# HP4-1.net
KiCad netlist of a schematic drawn in EAGLE
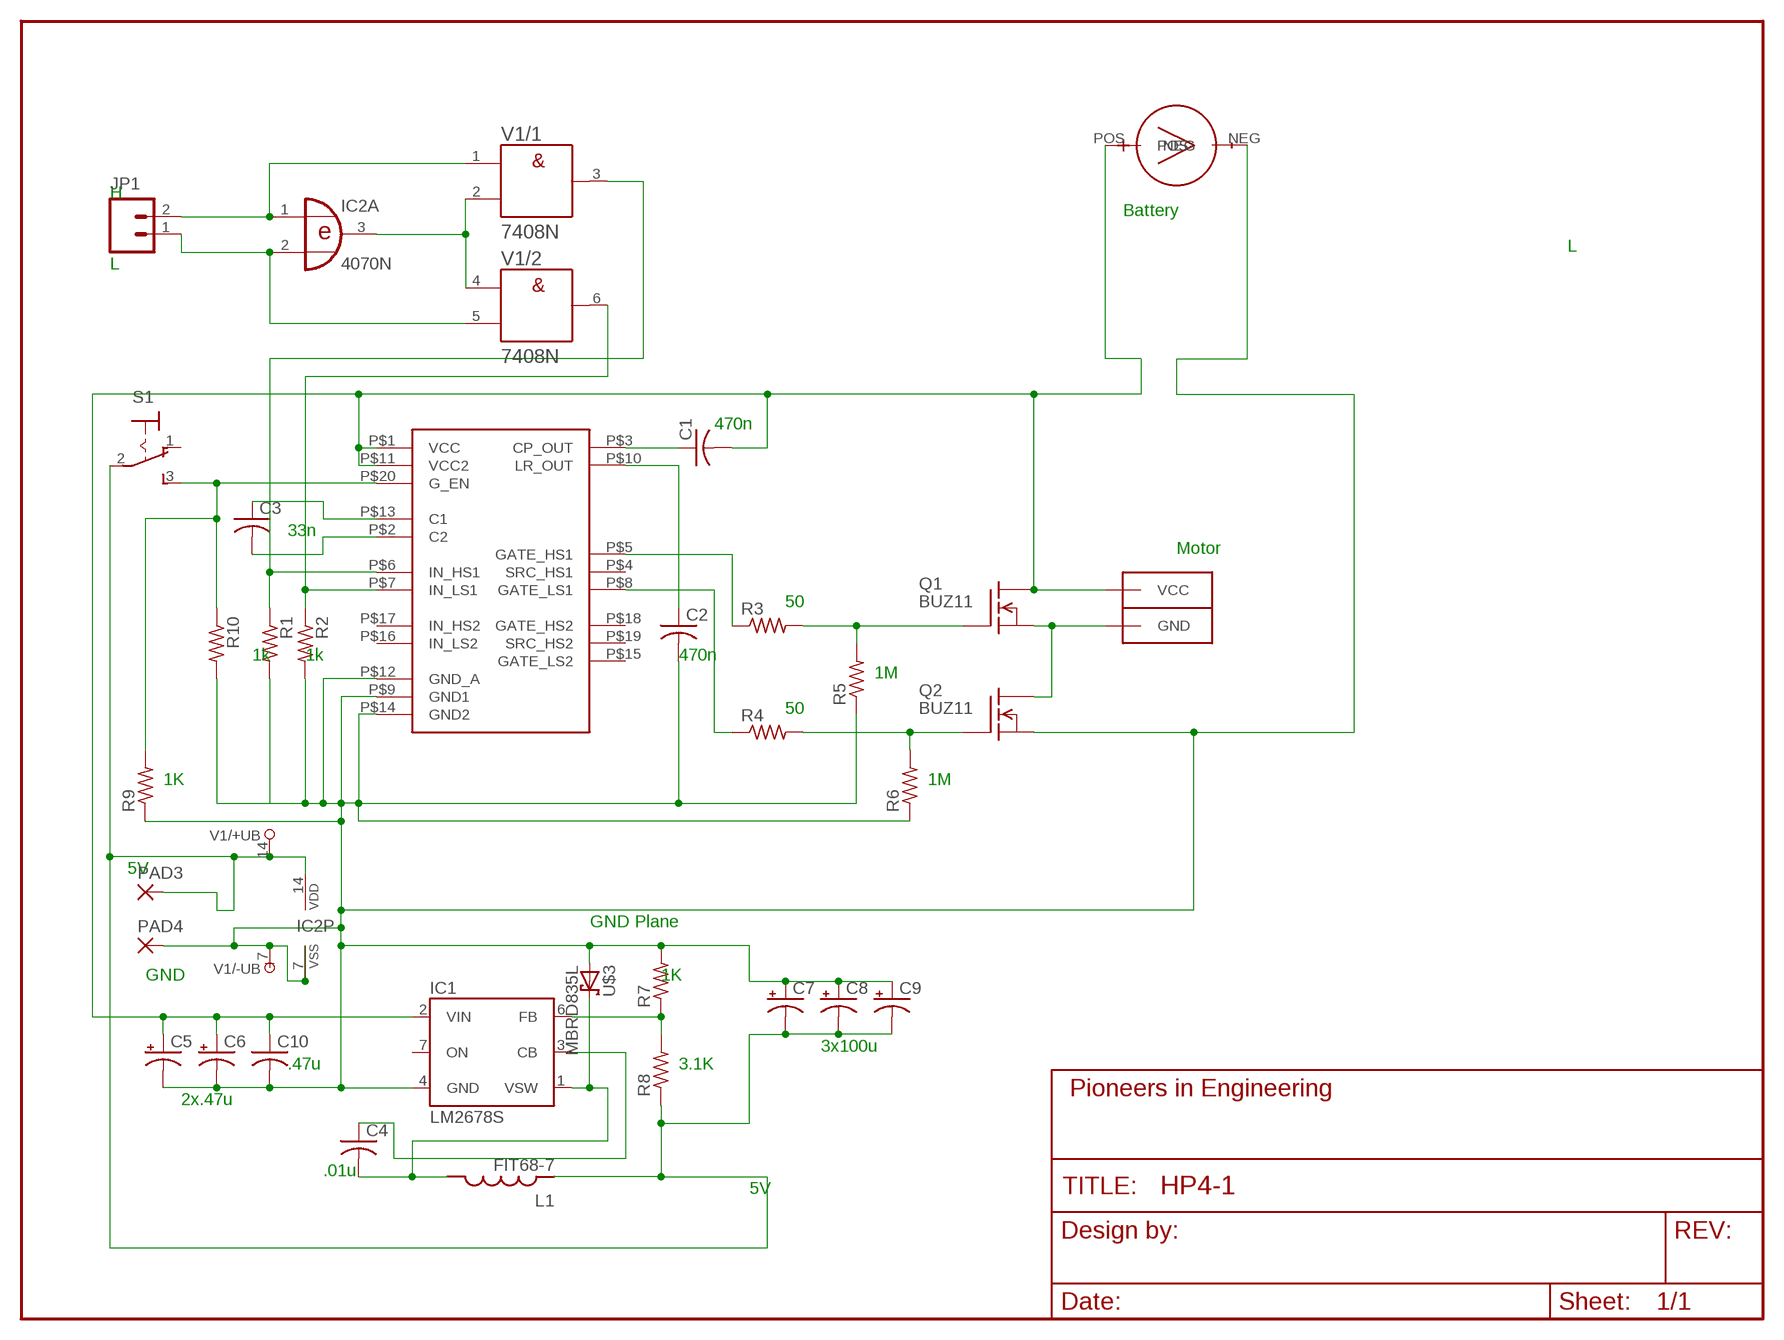
[diagram p0: schematic, sheet 1]

(export (version "E")
  (design (tool "Eeschema 10.0.6"))
  (components
    (comp (ref "C1")
      (value "C-USC1206")
      (footprint "eagle-import:C1206")
      (libsource (lib "eagle-import") (part "C-USC1206"))
    )
    (comp (ref "C2")
      (value "C-USC1206")
      (footprint "eagle-import:C1206")
      (libsource (lib "eagle-import") (part "C-USC1206"))
    )
    (comp (ref "C3")
      (value "C-USC1206")
      (footprint "eagle-import:C1206")
      (libsource (lib "eagle-import") (part "C-USC1206"))
    )
    (comp (ref "C4")
      (value "C-US025-024X044")
      (footprint "eagle-import:C025-024X044")
      (libsource (lib "eagle-import") (part "C-US025-024X044"))
    )
    (comp (ref "C5")
      (value "CPOL-USCT6032")
      (footprint "eagle-import:CT6032")
      (libsource (lib "eagle-import") (part "CPOL-USCT6032"))
    )
    (comp (ref "C6")
      (value "CPOL-USCT6032")
      (footprint "eagle-import:CT6032")
      (libsource (lib "eagle-import") (part "CPOL-USCT6032"))
    )
    (comp (ref "C7")
      (value "CPOL-USCT6032")
      (footprint "eagle-import:CT6032")
      (libsource (lib "eagle-import") (part "CPOL-USCT6032"))
    )
    (comp (ref "C8")
      (value "CPOL-USCT6032")
      (footprint "eagle-import:CT6032")
      (libsource (lib "eagle-import") (part "CPOL-USCT6032"))
    )
    (comp (ref "C9")
      (value "CPOL-USCT6032")
      (footprint "eagle-import:CT6032")
      (libsource (lib "eagle-import") (part "CPOL-USCT6032"))
    )
    (comp (ref "C10")
      (value "C-USC1206")
      (footprint "eagle-import:C1206")
      (libsource (lib "eagle-import") (part "C-USC1206"))
    )
    (comp (ref "IC1")
      (value "LM2678S")
      (footprint "eagle-import:TO263-7")
      (libsource (lib "eagle-import") (part "LM2678S"))
    )
    (comp (ref "IC2")
      (value "4070N")
      (footprint "eagle-import:DIL14")
      (libsource (lib "eagle-import") (part "4070N"))
    )
    (comp (ref "JP1")
      (value "M02PTH")
      (footprint "eagle-import:1X02")
      (libsource (lib "eagle-import") (part "M02PTH"))
    )
    (comp (ref "L1")
      (value "FIT68-7")
      (footprint "eagle-import:FIT68-7")
      (libsource (lib "eagle-import") (part "FIT68-7"))
    )
    (comp (ref "MOTOR")
      (value "ANDERSON_PP_DOUBLEHORIZONTAL")
      (footprint "eagle-import:ANDERSON_PP_DOUB_HORZ")
      (libsource (lib "eagle-import") (part "ANDERSON_PP_DOUBLEHORIZONTAL"))
    )
    (comp (ref "PAD3")
      (value "3,17/1,3")
      (footprint "eagle-import:3,17_1,3")
      (libsource (lib "eagle-import") (part "3,17/1,3"))
    )
    (comp (ref "PAD4")
      (value "3,17/1,3")
      (footprint "eagle-import:3,17_1,3")
      (libsource (lib "eagle-import") (part "3,17/1,3"))
    )
    (comp (ref "Q1")
      (value "BUZ11")
      (footprint "eagle-import:TO220")
      (libsource (lib "eagle-import") (part "BUZ11"))
    )
    (comp (ref "Q2")
      (value "BUZ11")
      (footprint "eagle-import:TO220")
      (libsource (lib "eagle-import") (part "BUZ11"))
    )
    (comp (ref "R1")
      (value "R-US_M1206")
      (footprint "eagle-import:M1206")
      (libsource (lib "eagle-import") (part "R-US_M1206"))
    )
    (comp (ref "R2")
      (value "R-US_M1206")
      (footprint "eagle-import:M1206")
      (libsource (lib "eagle-import") (part "R-US_M1206"))
    )
    (comp (ref "R3")
      (value "R-US_M1206")
      (footprint "eagle-import:M1206")
      (libsource (lib "eagle-import") (part "R-US_M1206"))
    )
    (comp (ref "R4")
      (value "R-US_M1206")
      (footprint "eagle-import:M1206")
      (libsource (lib "eagle-import") (part "R-US_M1206"))
    )
    (comp (ref "R5")
      (value "R-US_M1206")
      (footprint "eagle-import:M1206")
      (libsource (lib "eagle-import") (part "R-US_M1206"))
    )
    (comp (ref "R6")
      (value "R-US_M1206")
      (footprint "eagle-import:M1206")
      (libsource (lib "eagle-import") (part "R-US_M1206"))
    )
    (comp (ref "R7")
      (value "R-US_R1206")
      (footprint "eagle-import:R1206")
      (libsource (lib "eagle-import") (part "R-US_R1206"))
    )
    (comp (ref "R8")
      (value "R-US_R1206")
      (footprint "eagle-import:R1206")
      (libsource (lib "eagle-import") (part "R-US_R1206"))
    )
    (comp (ref "R9")
      (value "R-US_R1206")
      (footprint "eagle-import:R1206")
      (libsource (lib "eagle-import") (part "R-US_R1206"))
    )
    (comp (ref "R10")
      (value "R-US_M1206")
      (footprint "eagle-import:M1206")
      (libsource (lib "eagle-import") (part "R-US_M1206"))
    )
    (comp (ref "S1")
      (value "320-916")
      (footprint "eagle-import:320-916")
      (libsource (lib "eagle-import") (part "320-916"))
    )
    (comp (ref "U$1")
      (value "MC33883DIL20_600MIL_CARRIER")
      (footprint "eagle-import:DIL20_600MIL")
      (libsource (lib "eagle-import") (part "MC33883DIL20_600MIL_CARRIER"))
    )
    (comp (ref "U$3")
      (value "MBRD835L")
      (footprint "eagle-import:DPAK")
      (libsource (lib "eagle-import") (part "MBRD835L"))
    )
    (comp (ref "U$4")
      (value "BATT")
      (footprint "eagle-import:BATT")
      (libsource (lib "eagle-import") (part "BATT"))
    )
    (comp (ref "V1")
      (value "7408N")
      (footprint "eagle-import:DIL14")
      (libsource (lib "eagle-import") (part "7408N"))
    )
  )
  (nets
    (net (code "1") (name "Net-(IC1-CB)") (class "Default")
      (node (ref "C4") (pin "1") (pinfunction "1_1") (pintype "passive"))
      (node (ref "IC1") (pin "3") (pinfunction "CB_3") (pintype "input"))
    )
    (net (code "2") (name "Net-(IC1-FB)") (class "Default")
      (node (ref "IC1") (pin "6") (pinfunction "FB_6") (pintype "input"))
      (node (ref "R7") (pin "1") (pinfunction "1_1") (pintype "passive"))
      (node (ref "R8") (pin "2") (pinfunction "2_2") (pintype "passive"))
    )
    (net (code "3") (name "Net-(IC1-GND)") (class "Default")
      (node (ref "C10") (pin "2") (pinfunction "2_2") (pintype "passive"))
      (node (ref "C2") (pin "2") (pinfunction "2_2") (pintype "passive"))
      (node (ref "C5") (pin "-") (pinfunction "-_-") (pintype "passive"))
      (node (ref "C6") (pin "-") (pinfunction "-_-") (pintype "passive"))
      (node (ref "C7") (pin "+") (pinfunction "+_+") (pintype "passive"))
      (node (ref "C8") (pin "+") (pinfunction "+_+") (pintype "passive"))
      (node (ref "C9") (pin "+") (pinfunction "+_+") (pintype "passive"))
      (node (ref "IC1") (pin "4") (pinfunction "GND_4") (pintype "power_in"))
      (node (ref "IC2") (pin "7") (pinfunction "VSS_7") (pintype "power_in"))
      (node (ref "PAD4") (pin "1") (pinfunction "P_1") (pintype "passive"))
      (node (ref "Q2") (pin "3") (pinfunction "S_3") (pintype "passive"))
      (node (ref "R1") (pin "2") (pinfunction "2_2") (pintype "passive"))
      (node (ref "R10") (pin "2") (pinfunction "2_2") (pintype "passive"))
      (node (ref "R2") (pin "2") (pinfunction "2_2") (pintype "passive"))
      (node (ref "R5") (pin "1") (pinfunction "1_1") (pintype "passive"))
      (node (ref "R6") (pin "1") (pinfunction "1_1") (pintype "passive"))
      (node (ref "R7") (pin "2") (pinfunction "2_2") (pintype "passive"))
      (node (ref "R9") (pin "1") (pinfunction "1_1") (pintype "passive"))
      (node (ref "U$1") (pin "P$12") (pinfunction "GND_A_P$12") (pintype "bidirectional"))
      (node (ref "U$1") (pin "P$14") (pinfunction "GND2_P$14") (pintype "bidirectional"))
      (node (ref "U$1") (pin "P$9") (pinfunction "GND1_P$9") (pintype "bidirectional"))
      (node (ref "U$3") (pin "P$1") (pinfunction "A_P$1") (pintype "passive"))
      (node (ref "U$3") (pin "P$2") (pinfunction "A_P$2") (pintype "passive"))
      (node (ref "U$4") (pin "NEG") (pinfunction "NEG_NEG") (pintype "bidirectional"))
      (node (ref "V1") (pin "7") (pinfunction "-UB_7") (pintype "power_in"))
    )
    (net (code "4") (name "Net-(IC1-VIN)") (class "Default")
      (node (ref "C1") (pin "2") (pinfunction "2_2") (pintype "passive"))
      (node (ref "C10") (pin "1") (pinfunction "1_1") (pintype "passive"))
      (node (ref "C5") (pin "+") (pinfunction "+_+") (pintype "passive"))
      (node (ref "C6") (pin "+") (pinfunction "+_+") (pintype "passive"))
      (node (ref "IC1") (pin "2") (pinfunction "VIN_2") (pintype "power_in"))
      (node (ref "MOTOR") (pin "PIN2") (pinfunction "VCC_PIN2") (pintype "bidirectional"))
      (node (ref "MOTOR") (pin "PIN2-LEAD") (pinfunction "VCC_PIN2-LEAD") (pintype "bidirectional"))
      (node (ref "Q1") (pin "2") (pinfunction "D_2") (pintype "passive"))
      (node (ref "U$1") (pin "P$1") (pinfunction "VCC_P$1") (pintype "bidirectional"))
      (node (ref "U$1") (pin "P$11") (pinfunction "VCC2_P$11") (pintype "bidirectional"))
      (node (ref "U$4") (pin "POS") (pinfunction "POS_POS") (pintype "bidirectional"))
    )
    (net (code "5") (name "Net-(IC1-VSW)") (class "Default")
      (node (ref "C4") (pin "2") (pinfunction "2_2") (pintype "passive"))
      (node (ref "IC1") (pin "1") (pinfunction "VSW_1") (pintype "output"))
      (node (ref "L1") (pin "P$2") (pinfunction "P$2_P$2") (pintype "bidirectional"))
      (node (ref "U$3") (pin "P$3") (pinfunction "C_P$3") (pintype "passive"))
    )
    (net (code "6") (name "Net-(IC2A-I0)") (class "Default")
      (node (ref "IC2") (pin "1") (pinfunction "I0_1") (pintype "input"))
      (node (ref "JP1") (pin "2") (pinfunction "2_2") (pintype "passive"))
      (node (ref "V1") (pin "1") (pinfunction "A_1") (pintype "input"))
    )
    (net (code "7") (name "Net-(IC2A-I1)") (class "Default")
      (node (ref "IC2") (pin "2") (pinfunction "I1_2") (pintype "input"))
      (node (ref "JP1") (pin "1") (pinfunction "1_1") (pintype "passive"))
      (node (ref "V1") (pin "5") (pinfunction "B_5") (pintype "input"))
    )
    (net (code "8") (name "Net-(IC2A-O)") (class "Default")
      (node (ref "IC2") (pin "3") (pinfunction "O_3") (pintype "output"))
      (node (ref "V1") (pin "2") (pinfunction "B_2") (pintype "input"))
      (node (ref "V1") (pin "4") (pinfunction "A_4") (pintype "input"))
    )
    (net (code "9") (name "Net-(IC2E-VDD)") (class "Default")
      (node (ref "C7") (pin "-") (pinfunction "-_-") (pintype "passive"))
      (node (ref "C8") (pin "-") (pinfunction "-_-") (pintype "passive"))
      (node (ref "C9") (pin "-") (pinfunction "-_-") (pintype "passive"))
      (node (ref "IC2") (pin "14") (pinfunction "VDD_14") (pintype "power_in"))
      (node (ref "L1") (pin "P$1") (pinfunction "P$1_P$1") (pintype "bidirectional"))
      (node (ref "PAD3") (pin "1") (pinfunction "P_1") (pintype "passive"))
      (node (ref "R8") (pin "1") (pinfunction "1_1") (pintype "passive"))
      (node (ref "S1") (pin "2") (pinfunction "P_2") (pintype "passive"))
      (node (ref "V1") (pin "14") (pinfunction "+UB_14") (pintype "power_in"))
    )
    (net (code "10") (name "Net-(Q1-G)") (class "Default")
      (node (ref "Q1") (pin "1") (pinfunction "G_1") (pintype "passive"))
      (node (ref "R3") (pin "2") (pinfunction "2_2") (pintype "passive"))
      (node (ref "R5") (pin "2") (pinfunction "2_2") (pintype "passive"))
    )
    (net (code "11") (name "Net-(Q1-S)") (class "Default")
      (node (ref "MOTOR") (pin "PIN1") (pinfunction "GND_PIN1") (pintype "bidirectional"))
      (node (ref "MOTOR") (pin "PIN1-LEAD") (pinfunction "GND_PIN1-LEAD") (pintype "bidirectional"))
      (node (ref "Q1") (pin "3") (pinfunction "S_3") (pintype "passive"))
      (node (ref "Q2") (pin "2") (pinfunction "D_2") (pintype "passive"))
    )
    (net (code "12") (name "Net-(Q2-G)") (class "Default")
      (node (ref "Q2") (pin "1") (pinfunction "G_1") (pintype "passive"))
      (node (ref "R4") (pin "2") (pinfunction "2_2") (pintype "passive"))
      (node (ref "R6") (pin "2") (pinfunction "2_2") (pintype "passive"))
    )
    (net (code "13") (name "Net-(S1-S)") (class "Default")
      (node (ref "R10") (pin "1") (pinfunction "1_1") (pintype "passive"))
      (node (ref "R9") (pin "2") (pinfunction "2_2") (pintype "passive"))
      (node (ref "S1") (pin "3") (pinfunction "S_3") (pintype "passive"))
      (node (ref "U$1") (pin "P$20") (pinfunction "G_EN_P$20") (pintype "bidirectional"))
    )
    (net (code "14") (name "Net-(U$1-C1)") (class "Default")
      (node (ref "C3") (pin "1") (pinfunction "1_1") (pintype "passive"))
      (node (ref "U$1") (pin "P$13") (pinfunction "C1_P$13") (pintype "bidirectional"))
    )
    (net (code "15") (name "Net-(U$1-C2)") (class "Default")
      (node (ref "C3") (pin "2") (pinfunction "2_2") (pintype "passive"))
      (node (ref "U$1") (pin "P$2") (pinfunction "C2_P$2") (pintype "bidirectional"))
    )
    (net (code "16") (name "Net-(U$1-CP_OUT)") (class "Default")
      (node (ref "C1") (pin "1") (pinfunction "1_1") (pintype "passive"))
      (node (ref "U$1") (pin "P$3") (pinfunction "CP_OUT_P$3") (pintype "bidirectional"))
    )
    (net (code "17") (name "Net-(U$1-GATE_HS1)") (class "Default")
      (node (ref "R3") (pin "1") (pinfunction "1_1") (pintype "passive"))
      (node (ref "U$1") (pin "P$5") (pinfunction "GATE_HS1_P$5") (pintype "bidirectional"))
    )
    (net (code "18") (name "Net-(U$1-GATE_LS1)") (class "Default")
      (node (ref "R4") (pin "1") (pinfunction "1_1") (pintype "passive"))
      (node (ref "U$1") (pin "P$8") (pinfunction "GATE_LS1_P$8") (pintype "bidirectional"))
    )
    (net (code "19") (name "Net-(U$1-IN_HS1)") (class "Default")
      (node (ref "R1") (pin "1") (pinfunction "1_1") (pintype "passive"))
      (node (ref "U$1") (pin "P$6") (pinfunction "IN_HS1_P$6") (pintype "bidirectional"))
      (node (ref "V1") (pin "3") (pinfunction "Y_3") (pintype "output"))
    )
    (net (code "20") (name "Net-(U$1-IN_LS1)") (class "Default")
      (node (ref "R2") (pin "1") (pinfunction "1_1") (pintype "passive"))
      (node (ref "U$1") (pin "P$7") (pinfunction "IN_LS1_P$7") (pintype "bidirectional"))
      (node (ref "V1") (pin "6") (pinfunction "Y_6") (pintype "output"))
    )
    (net (code "21") (name "Net-(U$1-LR_OUT)") (class "Default")
      (node (ref "C2") (pin "1") (pinfunction "1_1") (pintype "passive"))
      (node (ref "U$1") (pin "P$10") (pinfunction "LR_OUT_P$10") (pintype "bidirectional"))
    )
    (net (code "22") (name "unconnected-(IC1-ON-Pad7)") (class "Default")
      (node (ref "IC1") (pin "7") (pinfunction "ON_7") (pintype "passive"))
    )
    (net (code "23") (name "unconnected-(S1-O-Pad1)") (class "Default")
      (node (ref "S1") (pin "1") (pinfunction "O_1") (pintype "passive"))
    )
    (net (code "24") (name "unconnected-(U$1-GATE_HS2-PadP$18)") (class "Default")
      (node (ref "U$1") (pin "P$18") (pinfunction "GATE_HS2_P$18") (pintype "bidirectional"))
    )
    (net (code "25") (name "unconnected-(U$1-GATE_LS2-PadP$15)") (class "Default")
      (node (ref "U$1") (pin "P$15") (pinfunction "GATE_LS2_P$15") (pintype "bidirectional"))
    )
    (net (code "26") (name "unconnected-(U$1-IN_HS2-PadP$17)") (class "Default")
      (node (ref "U$1") (pin "P$17") (pinfunction "IN_HS2_P$17") (pintype "bidirectional"))
    )
    (net (code "27") (name "unconnected-(U$1-IN_LS2-PadP$16)") (class "Default")
      (node (ref "U$1") (pin "P$16") (pinfunction "IN_LS2_P$16") (pintype "bidirectional"))
    )
    (net (code "28") (name "unconnected-(U$1-SRC_HS1-PadP$4)") (class "Default")
      (node (ref "U$1") (pin "P$4") (pinfunction "SRC_HS1_P$4") (pintype "bidirectional"))
    )
    (net (code "29") (name "unconnected-(U$1-SRC_HS2-PadP$19)") (class "Default")
      (node (ref "U$1") (pin "P$19") (pinfunction "SRC_HS2_P$19") (pintype "bidirectional"))
    )
  )
)
